# RS485_Channel_4.net
KiCad netlist of a schematic drawn in Altium Designer
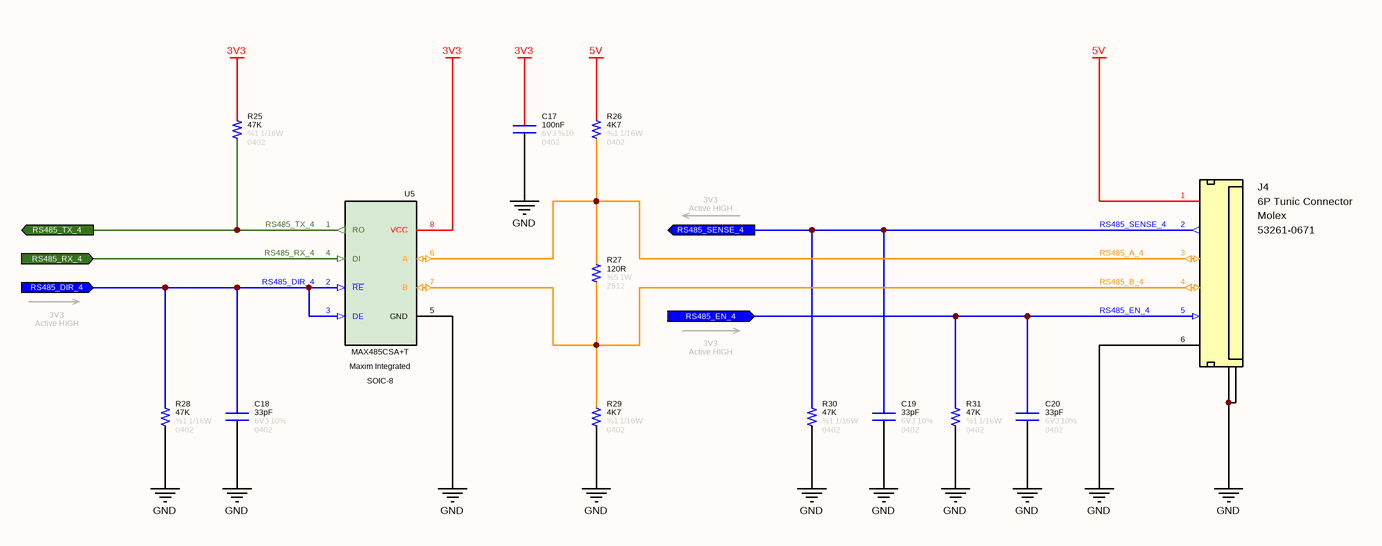
[diagram p0: RS485 Channel 4.SchDoc]

(export (version "E")
  (design (tool "Eeschema 10.0.6"))
  (components
    (comp (ref "C17")
      (value "100nF")
      (footprint "CAPACITOR_0402")
      (description "Capacitor - 100nF [0402-6V3] (Ceramic)")
      (fields
        (field (name "MANUFACTURER PART NUMBER") "04026D104KAT4A")
        (field (name "TOLERANCE") "%10")
        (field (name "VOLTAGE") "6V3")
        (field (name "CASE") "0402")
        (field (name "Comment") "Capacitor - 100nF [0402] (Ceramic)")
      )
      (libsource (lib "Akkoyun") (part "Capacitor - 100nF [0402-6V3]"))
    )
    (comp (ref "C18")
      (value "33pF")
      (footprint "CAPACITOR_0402")
      (description "Capacitor - 33pF [0402] (Ceramic)")
      (fields
        (field (name "MANUFACTURER PART NUMBER") "C0402C330J9RACAUTO")
        (field (name "TOLERANCE") "10%")
        (field (name "CASE") "0402")
        (field (name "VOLTAGE") "6V3")
      )
      (libsource (lib "Akkoyun") (part "Capacitor - 33pF [0402-6V3]"))
    )
    (comp (ref "C19")
      (value "33pF")
      (footprint "CAPACITOR_0402")
      (description "Capacitor - 33pF [0402] (Ceramic)")
      (fields
        (field (name "MANUFACTURER PART NUMBER") "C0402C330J9RACAUTO")
        (field (name "TOLERANCE") "10%")
        (field (name "CASE") "0402")
        (field (name "VOLTAGE") "6V3")
      )
      (libsource (lib "Akkoyun") (part "Capacitor - 33pF [0402-6V3]"))
    )
    (comp (ref "C20")
      (value "33pF")
      (footprint "CAPACITOR_0402")
      (description "Capacitor - 33pF [0402] (Ceramic)")
      (fields
        (field (name "MANUFACTURER PART NUMBER") "C0402C330J9RACAUTO")
        (field (name "TOLERANCE") "10%")
        (field (name "CASE") "0402")
        (field (name "VOLTAGE") "6V3")
      )
      (libsource (lib "Akkoyun") (part "Capacitor - 33pF [0402-6V3]"))
    )
    (comp (ref "J4")
      (value "6P Tunic Connector")
      (footprint "Connector_Tunic 6P")
      (description "Mini Tunic Connector with 6P")
      (fields
        (field (name "MANUFACTURER PART NUMBER") "53261-0671")
        (field (name "MANUFACTURER NAME") "Molex")
      )
      (libsource (lib "Akkoyun") (part "Connector - Mini Tunic 6P (1.25)"))
    )
    (comp (ref "R25")
      (value "47K")
      (footprint "RESISTOR_0402")
      (description "Thick Film Resistors - SMD 1/16 W 47 KOhm 1%")
      (fields
        (field (name "MANUFACTURER PART NUMBER") "CRCW040247K0FKED")
        (field (name "TOLERANCE") "%1")
        (field (name "CASE") "0402")
        (field (name "POWER") "1/16W")
        (field (name "Comment") "47K - 0402 - %1 - 1/16W")
      )
      (libsource (lib "Akkoyun") (part "Resistor - 47K [0402]"))
    )
    (comp (ref "R26")
      (value "4K7")
      (footprint "RESISTOR_0402")
      (description "Thick Film Resistors - SMD 1/16 W 4.7 KOhm 1%")
      (fields
        (field (name "MANUFACTURER PART NUMBER") "CRCW04024K70FKED")
        (field (name "TOLERANCE") "%1")
        (field (name "CASE") "0402")
        (field (name "POWER") "1/16W")
        (field (name "Comment") "4K7 - 0402 - %1 - 1/16W")
      )
      (libsource (lib "Akkoyun") (part "Resistor - 4K7 [0402]"))
    )
    (comp (ref "R27")
      (value "120R")
      (footprint "RESISTOR_2512")
      (description "Thick Film Resistors - SMD 1 W 120 Ohm 5%")
      (fields
        (field (name "MANUFACTURER PART NUMBER") "RC2512JK-07120RL")
        (field (name "TOLERANCE") "%5")
        (field (name "CASE") "2512")
        (field (name "POWER") "1W")
        (field (name "Comment") "120R - 2512 - %5 - 1W")
      )
      (libsource (lib "Akkoyun") (part "Resistor - 120R [2512]"))
    )
    (comp (ref "R28")
      (value "47K")
      (footprint "RESISTOR_0402")
      (description "Thick Film Resistors - SMD 1/16 W 47 KOhm 1%")
      (fields
        (field (name "MANUFACTURER PART NUMBER") "CRCW040247K0FKED")
        (field (name "TOLERANCE") "%1")
        (field (name "CASE") "0402")
        (field (name "POWER") "1/16W")
        (field (name "Comment") "47K - 0402 - %1 - 1/16W")
      )
      (libsource (lib "Akkoyun") (part "Resistor - 47K [0402]"))
    )
    (comp (ref "R29")
      (value "4K7")
      (footprint "RESISTOR_0402")
      (description "Thick Film Resistors - SMD 1/16 W 4.7 KOhm 1%")
      (fields
        (field (name "MANUFACTURER PART NUMBER") "CRCW04024K70FKED")
        (field (name "TOLERANCE") "%1")
        (field (name "CASE") "0402")
        (field (name "POWER") "1/16W")
        (field (name "Comment") "4K7 - 0402 - %1 - 1/16W")
      )
      (libsource (lib "Akkoyun") (part "Resistor - 4K7 [0402]"))
    )
    (comp (ref "R30")
      (value "47K")
      (footprint "RESISTOR_0402")
      (description "Thick Film Resistors - SMD 1/16 W 47 KOhm 1%")
      (fields
        (field (name "MANUFACTURER PART NUMBER") "CRCW040247K0FKED")
        (field (name "TOLERANCE") "%1")
        (field (name "CASE") "0402")
        (field (name "POWER") "1/16W")
        (field (name "Comment") "47K - 0402 - %1 - 1/16W")
      )
      (libsource (lib "Akkoyun") (part "Resistor - 47K [0402]"))
    )
    (comp (ref "R31")
      (value "47K")
      (footprint "RESISTOR_0402")
      (description "Thick Film Resistors - SMD 1/16 W 47 KOhm 1%")
      (fields
        (field (name "MANUFACTURER PART NUMBER") "CRCW040247K0FKED")
        (field (name "TOLERANCE") "%1")
        (field (name "CASE") "0402")
        (field (name "POWER") "1/16W")
        (field (name "Comment") "47K - 0402 - %1 - 1/16W")
      )
      (libsource (lib "Akkoyun") (part "Resistor - 47K [0402]"))
    )
    (comp (ref "U5")
      (value "RS485 Modulator")
      (footprint "SOP-8L (AZRS3080E)")
      (description "RS-422/RS-485 Interface IC Low-Power, Slew-Rate-Limited RS-485/RS-422 Transceivers")
      (fields
        (field (name "CASE") "SOIC-8")
        (field (name "MANUFACTURER PART NUMBER") "MAX485CSA+T")
        (field (name "MANUFACTURER NAME") "Maxim Integrated")
      )
      (libsource (lib "Akkoyun") (part "IC - MAX485CSA+T"))
    )
  )
  (nets
    (net (code "1") (name "/RS485_A_4") (class "Default")
      (node (ref "J4") (pin "3") (pinfunction "RS485-A_3") (pintype "bidirectional"))
      (node (ref "R26") (pin "1") (pinfunction "1_1") (pintype "passive"))
      (node (ref "R27") (pin "2") (pinfunction "2_2") (pintype "passive"))
      (node (ref "U5") (pin "6") (pinfunction "A_6") (pintype "bidirectional"))
    )
    (net (code "2") (name "/RS485_B_4") (class "Default")
      (node (ref "J4") (pin "4") (pinfunction "RS485-B_4") (pintype "bidirectional"))
      (node (ref "R27") (pin "1") (pinfunction "1_1") (pintype "passive"))
      (node (ref "R29") (pin "2") (pinfunction "2_2") (pintype "passive"))
      (node (ref "U5") (pin "7") (pinfunction "B_7") (pintype "bidirectional"))
    )
    (net (code "3") (name "/RS485_DIR_4") (class "Default")
      (node (ref "C18") (pin "2") (pinfunction "2_2") (pintype "passive"))
      (node (ref "R28") (pin "2") (pinfunction "2_2") (pintype "passive"))
      (node (ref "U5") (pin "2") (pinfunction "~{RE}_2") (pintype "input"))
      (node (ref "U5") (pin "3") (pinfunction "DE_3") (pintype "input"))
    )
    (net (code "4") (name "/RS485_EN_4") (class "Default")
      (node (ref "C20") (pin "2") (pinfunction "2_2") (pintype "passive"))
      (node (ref "J4") (pin "5") (pinfunction "INT_5") (pintype "input"))
      (node (ref "R31") (pin "2") (pinfunction "2_2") (pintype "passive"))
    )
    (net (code "5") (name "/RS485_RX_4") (class "Default")
      (node (ref "U5") (pin "4") (pinfunction "DI_4") (pintype "input"))
    )
    (net (code "6") (name "/RS485_SENSE_4") (class "Default")
      (node (ref "C19") (pin "2") (pinfunction "2_2") (pintype "passive"))
      (node (ref "J4") (pin "2") (pinfunction "Sense_2") (pintype "output"))
      (node (ref "R30") (pin "2") (pinfunction "2_2") (pintype "passive"))
    )
    (net (code "7") (name "/RS485_TX_4") (class "Default")
      (node (ref "R25") (pin "1") (pinfunction "1_1") (pintype "passive"))
      (node (ref "U5") (pin "1") (pinfunction "RO_1") (pintype "output"))
    )
    (net (code "8") (name "3V3") (class "Default")
      (node (ref "C17") (pin "2") (pinfunction "2_2") (pintype "passive"))
      (node (ref "R25") (pin "2") (pinfunction "2_2") (pintype "passive"))
      (node (ref "U5") (pin "8") (pinfunction "VCC_8") (pintype "power_in"))
    )
    (net (code "9") (name "5V") (class "Default")
      (node (ref "J4") (pin "1") (pinfunction "5V_1") (pintype "power_in"))
      (node (ref "R26") (pin "2") (pinfunction "2_2") (pintype "passive"))
    )
    (net (code "10") (name "GND") (class "Default")
      (node (ref "C17") (pin "1") (pinfunction "1_1") (pintype "passive"))
      (node (ref "C18") (pin "1") (pinfunction "1_1") (pintype "passive"))
      (node (ref "C19") (pin "1") (pinfunction "1_1") (pintype "passive"))
      (node (ref "C20") (pin "1") (pinfunction "1_1") (pintype "passive"))
      (node (ref "J4") (pin "6") (pinfunction "GND_6") (pintype "power_in"))
      (node (ref "J4") (pin "7") (pinfunction "GND_7") (pintype "passive"))
      (node (ref "J4") (pin "8") (pinfunction "GND_8") (pintype "passive"))
      (node (ref "R28") (pin "1") (pinfunction "1_1") (pintype "passive"))
      (node (ref "R29") (pin "1") (pinfunction "1_1") (pintype "passive"))
      (node (ref "R30") (pin "1") (pinfunction "1_1") (pintype "passive"))
      (node (ref "R31") (pin "1") (pinfunction "1_1") (pintype "passive"))
      (node (ref "U5") (pin "5") (pinfunction "GND_5") (pintype "passive"))
    )
  )
)
